# interface.net
KiCad netlist of a schematic drawn in Altium Designer
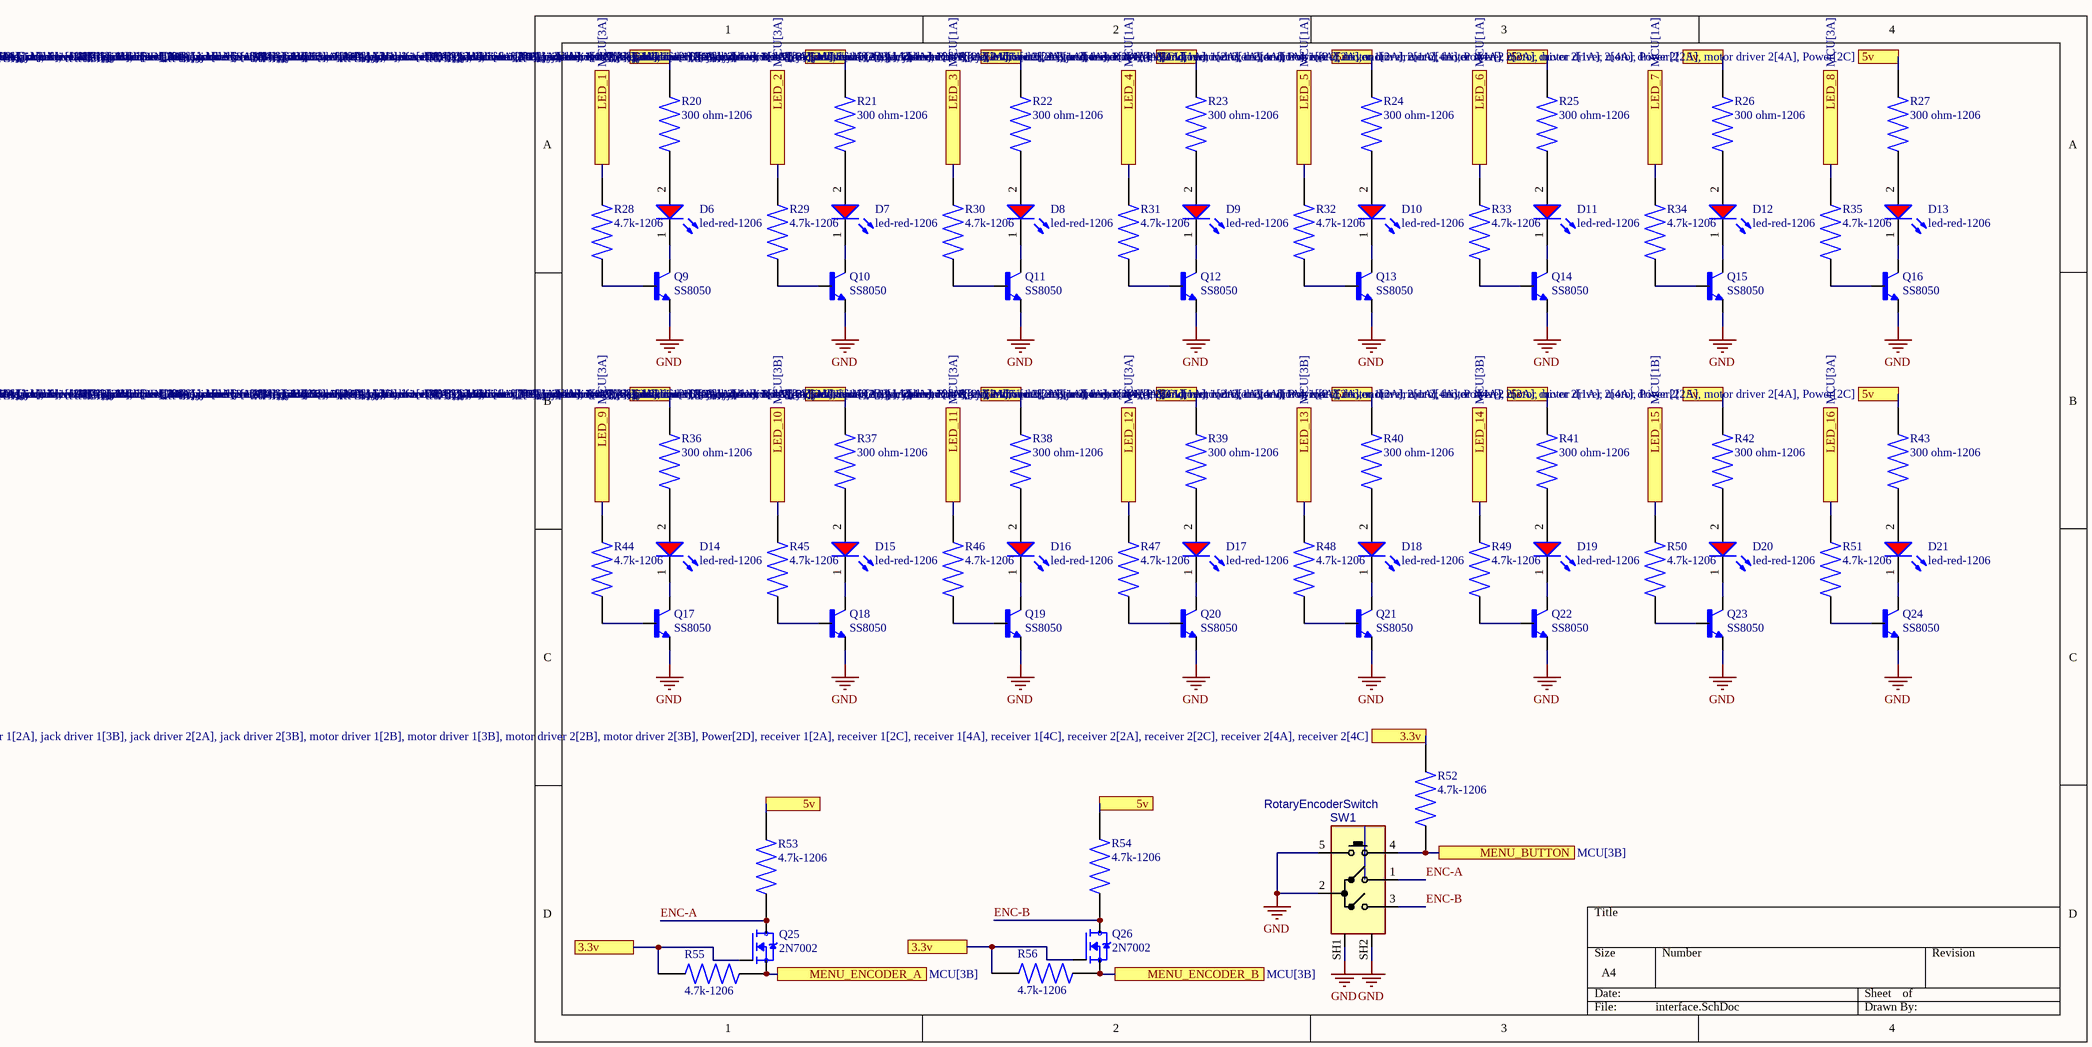
[diagram p0: interface.SchDoc]

(export (version "E")
  (design (tool "Eeschema 10.0.6"))
  (components
    (comp (ref "D6")
      (value "led-red-1206")
      (footprint "WL-SMRW_1206 dome_normal use")
      (description "WL-SMRW Mono-color Reverse mount Waterclear, SMT, size 1206 dome, Red, 2V, 20°")
      (fields
        (field (name "MANUFACTURER PART NUMBER") "156120RS82500")
        (field (name "MANUFACTURER") "Wurth Elektronik")
      )
      (libsource (lib "led-1206") (part "156120RS82500"))
    )
    (comp (ref "D7")
      (value "led-red-1206")
      (footprint "WL-SMRW_1206 dome_normal use")
      (description "WL-SMRW Mono-color Reverse mount Waterclear, SMT, size 1206 dome, Red, 2V, 20°")
      (fields
        (field (name "MANUFACTURER PART NUMBER") "156120RS82500")
        (field (name "MANUFACTURER") "Wurth Elektronik")
      )
      (libsource (lib "led-1206") (part "156120RS82500"))
    )
    (comp (ref "D8")
      (value "led-red-1206")
      (footprint "WL-SMRW_1206 dome_normal use")
      (description "WL-SMRW Mono-color Reverse mount Waterclear, SMT, size 1206 dome, Red, 2V, 20°")
      (fields
        (field (name "MANUFACTURER PART NUMBER") "156120RS82500")
        (field (name "MANUFACTURER") "Wurth Elektronik")
      )
      (libsource (lib "led-1206") (part "156120RS82500"))
    )
    (comp (ref "D9")
      (value "led-red-1206")
      (footprint "WL-SMRW_1206 dome_normal use")
      (description "WL-SMRW Mono-color Reverse mount Waterclear, SMT, size 1206 dome, Red, 2V, 20°")
      (fields
        (field (name "MANUFACTURER PART NUMBER") "156120RS82500")
        (field (name "MANUFACTURER") "Wurth Elektronik")
      )
      (libsource (lib "led-1206") (part "156120RS82500"))
    )
    (comp (ref "D10")
      (value "led-red-1206")
      (footprint "WL-SMRW_1206 dome_normal use")
      (description "WL-SMRW Mono-color Reverse mount Waterclear, SMT, size 1206 dome, Red, 2V, 20°")
      (fields
        (field (name "MANUFACTURER PART NUMBER") "156120RS82500")
        (field (name "MANUFACTURER") "Wurth Elektronik")
      )
      (libsource (lib "led-1206") (part "156120RS82500"))
    )
    (comp (ref "D11")
      (value "led-red-1206")
      (footprint "WL-SMRW_1206 dome_normal use")
      (description "WL-SMRW Mono-color Reverse mount Waterclear, SMT, size 1206 dome, Red, 2V, 20°")
      (fields
        (field (name "MANUFACTURER PART NUMBER") "156120RS82500")
        (field (name "MANUFACTURER") "Wurth Elektronik")
      )
      (libsource (lib "led-1206") (part "156120RS82500"))
    )
    (comp (ref "D12")
      (value "led-red-1206")
      (footprint "WL-SMRW_1206 dome_normal use")
      (description "WL-SMRW Mono-color Reverse mount Waterclear, SMT, size 1206 dome, Red, 2V, 20°")
      (fields
        (field (name "MANUFACTURER PART NUMBER") "156120RS82500")
        (field (name "MANUFACTURER") "Wurth Elektronik")
      )
      (libsource (lib "led-1206") (part "156120RS82500"))
    )
    (comp (ref "D13")
      (value "led-red-1206")
      (footprint "WL-SMRW_1206 dome_normal use")
      (description "WL-SMRW Mono-color Reverse mount Waterclear, SMT, size 1206 dome, Red, 2V, 20°")
      (fields
        (field (name "MANUFACTURER PART NUMBER") "156120RS82500")
        (field (name "MANUFACTURER") "Wurth Elektronik")
      )
      (libsource (lib "led-1206") (part "156120RS82500"))
    )
    (comp (ref "D14")
      (value "led-red-1206")
      (footprint "WL-SMRW_1206 dome_normal use")
      (description "WL-SMRW Mono-color Reverse mount Waterclear, SMT, size 1206 dome, Red, 2V, 20°")
      (fields
        (field (name "MANUFACTURER PART NUMBER") "156120RS82500")
        (field (name "MANUFACTURER") "Wurth Elektronik")
      )
      (libsource (lib "led-1206") (part "156120RS82500"))
    )
    (comp (ref "D15")
      (value "led-red-1206")
      (footprint "WL-SMRW_1206 dome_normal use")
      (description "WL-SMRW Mono-color Reverse mount Waterclear, SMT, size 1206 dome, Red, 2V, 20°")
      (fields
        (field (name "MANUFACTURER PART NUMBER") "156120RS82500")
        (field (name "MANUFACTURER") "Wurth Elektronik")
      )
      (libsource (lib "led-1206") (part "156120RS82500"))
    )
    (comp (ref "D16")
      (value "led-red-1206")
      (footprint "WL-SMRW_1206 dome_normal use")
      (description "WL-SMRW Mono-color Reverse mount Waterclear, SMT, size 1206 dome, Red, 2V, 20°")
      (fields
        (field (name "MANUFACTURER PART NUMBER") "156120RS82500")
        (field (name "MANUFACTURER") "Wurth Elektronik")
      )
      (libsource (lib "led-1206") (part "156120RS82500"))
    )
    (comp (ref "D17")
      (value "led-red-1206")
      (footprint "WL-SMRW_1206 dome_normal use")
      (description "WL-SMRW Mono-color Reverse mount Waterclear, SMT, size 1206 dome, Red, 2V, 20°")
      (fields
        (field (name "MANUFACTURER PART NUMBER") "156120RS82500")
        (field (name "MANUFACTURER") "Wurth Elektronik")
      )
      (libsource (lib "led-1206") (part "156120RS82500"))
    )
    (comp (ref "D18")
      (value "led-red-1206")
      (footprint "WL-SMRW_1206 dome_normal use")
      (description "WL-SMRW Mono-color Reverse mount Waterclear, SMT, size 1206 dome, Red, 2V, 20°")
      (fields
        (field (name "MANUFACTURER PART NUMBER") "156120RS82500")
        (field (name "MANUFACTURER") "Wurth Elektronik")
      )
      (libsource (lib "led-1206") (part "156120RS82500"))
    )
    (comp (ref "D19")
      (value "led-red-1206")
      (footprint "WL-SMRW_1206 dome_normal use")
      (description "WL-SMRW Mono-color Reverse mount Waterclear, SMT, size 1206 dome, Red, 2V, 20°")
      (fields
        (field (name "MANUFACTURER PART NUMBER") "156120RS82500")
        (field (name "MANUFACTURER") "Wurth Elektronik")
      )
      (libsource (lib "led-1206") (part "156120RS82500"))
    )
    (comp (ref "D20")
      (value "led-red-1206")
      (footprint "WL-SMRW_1206 dome_normal use")
      (description "WL-SMRW Mono-color Reverse mount Waterclear, SMT, size 1206 dome, Red, 2V, 20°")
      (fields
        (field (name "MANUFACTURER PART NUMBER") "156120RS82500")
        (field (name "MANUFACTURER") "Wurth Elektronik")
      )
      (libsource (lib "led-1206") (part "156120RS82500"))
    )
    (comp (ref "D21")
      (value "led-red-1206")
      (footprint "WL-SMRW_1206 dome_normal use")
      (description "WL-SMRW Mono-color Reverse mount Waterclear, SMT, size 1206 dome, Red, 2V, 20°")
      (fields
        (field (name "MANUFACTURER PART NUMBER") "156120RS82500")
        (field (name "MANUFACTURER") "Wurth Elektronik")
      )
      (libsource (lib "led-1206") (part "156120RS82500"))
    )
    (comp (ref "Q9")
      (value "SS8050")
      (footprint "TRANS_SS8050-G")
      (description "Bipolar (BJT) Transistor NPN 25 V 1.5 A 100MHz 300 mW Surface Mount SOT-23-3")
      (fields (field (name "DIGI-KEY_PART_NUMBER") "641-1790-2-ND") (field (name "MP") "SS8050G"))
      (libsource (lib "SS8050-G") (part "SS8050-G"))
    )
    (comp (ref "Q10")
      (value "SS8050")
      (footprint "TRANS_SS8050-G")
      (description "Bipolar (BJT) Transistor NPN 25 V 1.5 A 100MHz 300 mW Surface Mount SOT-23-3")
      (fields (field (name "DIGI-KEY_PART_NUMBER") "641-1790-2-ND") (field (name "MP") "SS8050G"))
      (libsource (lib "SS8050-G") (part "SS8050-G"))
    )
    (comp (ref "Q11")
      (value "SS8050")
      (footprint "TRANS_SS8050-G")
      (description "Bipolar (BJT) Transistor NPN 25 V 1.5 A 100MHz 300 mW Surface Mount SOT-23-3")
      (fields (field (name "DIGI-KEY_PART_NUMBER") "641-1790-2-ND") (field (name "MP") "SS8050G"))
      (libsource (lib "SS8050-G") (part "SS8050-G"))
    )
    (comp (ref "Q12")
      (value "SS8050")
      (footprint "TRANS_SS8050-G")
      (description "Bipolar (BJT) Transistor NPN 25 V 1.5 A 100MHz 300 mW Surface Mount SOT-23-3")
      (fields (field (name "DIGI-KEY_PART_NUMBER") "641-1790-2-ND") (field (name "MP") "SS8050G"))
      (libsource (lib "SS8050-G") (part "SS8050-G"))
    )
    (comp (ref "Q13")
      (value "SS8050")
      (footprint "TRANS_SS8050-G")
      (description "Bipolar (BJT) Transistor NPN 25 V 1.5 A 100MHz 300 mW Surface Mount SOT-23-3")
      (fields (field (name "DIGI-KEY_PART_NUMBER") "641-1790-2-ND") (field (name "MP") "SS8050G"))
      (libsource (lib "SS8050-G") (part "SS8050-G"))
    )
    (comp (ref "Q14")
      (value "SS8050")
      (footprint "TRANS_SS8050-G")
      (description "Bipolar (BJT) Transistor NPN 25 V 1.5 A 100MHz 300 mW Surface Mount SOT-23-3")
      (fields (field (name "DIGI-KEY_PART_NUMBER") "641-1790-2-ND") (field (name "MP") "SS8050G"))
      (libsource (lib "SS8050-G") (part "SS8050-G"))
    )
    (comp (ref "Q15")
      (value "SS8050")
      (footprint "TRANS_SS8050-G")
      (description "Bipolar (BJT) Transistor NPN 25 V 1.5 A 100MHz 300 mW Surface Mount SOT-23-3")
      (fields (field (name "DIGI-KEY_PART_NUMBER") "641-1790-2-ND") (field (name "MP") "SS8050G"))
      (libsource (lib "SS8050-G") (part "SS8050-G"))
    )
    (comp (ref "Q16")
      (value "SS8050")
      (footprint "TRANS_SS8050-G")
      (description "Bipolar (BJT) Transistor NPN 25 V 1.5 A 100MHz 300 mW Surface Mount SOT-23-3")
      (fields (field (name "DIGI-KEY_PART_NUMBER") "641-1790-2-ND") (field (name "MP") "SS8050G"))
      (libsource (lib "SS8050-G") (part "SS8050-G"))
    )
    (comp (ref "Q17")
      (value "SS8050")
      (footprint "TRANS_SS8050-G")
      (description "Bipolar (BJT) Transistor NPN 25 V 1.5 A 100MHz 300 mW Surface Mount SOT-23-3")
      (fields (field (name "DIGI-KEY_PART_NUMBER") "641-1790-2-ND") (field (name "MP") "SS8050G"))
      (libsource (lib "SS8050-G") (part "SS8050-G"))
    )
    (comp (ref "Q18")
      (value "SS8050")
      (footprint "TRANS_SS8050-G")
      (description "Bipolar (BJT) Transistor NPN 25 V 1.5 A 100MHz 300 mW Surface Mount SOT-23-3")
      (fields (field (name "DIGI-KEY_PART_NUMBER") "641-1790-2-ND") (field (name "MP") "SS8050G"))
      (libsource (lib "SS8050-G") (part "SS8050-G"))
    )
    (comp (ref "Q19")
      (value "SS8050")
      (footprint "TRANS_SS8050-G")
      (description "Bipolar (BJT) Transistor NPN 25 V 1.5 A 100MHz 300 mW Surface Mount SOT-23-3")
      (fields (field (name "DIGI-KEY_PART_NUMBER") "641-1790-2-ND") (field (name "MP") "SS8050G"))
      (libsource (lib "SS8050-G") (part "SS8050-G"))
    )
    (comp (ref "Q20")
      (value "SS8050")
      (footprint "TRANS_SS8050-G")
      (description "Bipolar (BJT) Transistor NPN 25 V 1.5 A 100MHz 300 mW Surface Mount SOT-23-3")
      (fields (field (name "DIGI-KEY_PART_NUMBER") "641-1790-2-ND") (field (name "MP") "SS8050G"))
      (libsource (lib "SS8050-G") (part "SS8050-G"))
    )
    (comp (ref "Q21")
      (value "SS8050")
      (footprint "TRANS_SS8050-G")
      (description "Bipolar (BJT) Transistor NPN 25 V 1.5 A 100MHz 300 mW Surface Mount SOT-23-3")
      (fields (field (name "DIGI-KEY_PART_NUMBER") "641-1790-2-ND") (field (name "MP") "SS8050G"))
      (libsource (lib "SS8050-G") (part "SS8050-G"))
    )
    (comp (ref "Q22")
      (value "SS8050")
      (footprint "TRANS_SS8050-G")
      (description "Bipolar (BJT) Transistor NPN 25 V 1.5 A 100MHz 300 mW Surface Mount SOT-23-3")
      (fields (field (name "DIGI-KEY_PART_NUMBER") "641-1790-2-ND") (field (name "MP") "SS8050G"))
      (libsource (lib "SS8050-G") (part "SS8050-G"))
    )
    (comp (ref "Q23")
      (value "SS8050")
      (footprint "TRANS_SS8050-G")
      (description "Bipolar (BJT) Transistor NPN 25 V 1.5 A 100MHz 300 mW Surface Mount SOT-23-3")
      (fields (field (name "DIGI-KEY_PART_NUMBER") "641-1790-2-ND") (field (name "MP") "SS8050G"))
      (libsource (lib "SS8050-G") (part "SS8050-G"))
    )
    (comp (ref "Q24")
      (value "SS8050")
      (footprint "TRANS_SS8050-G")
      (description "Bipolar (BJT) Transistor NPN 25 V 1.5 A 100MHz 300 mW Surface Mount SOT-23-3")
      (fields (field (name "DIGI-KEY_PART_NUMBER") "641-1790-2-ND") (field (name "MP") "SS8050G"))
      (libsource (lib "SS8050-G") (part "SS8050-G"))
    )
    (comp (ref "Q25")
      (value "2N7002")
      (footprint "SOT95P240X111-3N")
      (description "N-Channel 60V 280mA (Ta) 350mW (Ta) Surface Mount SOT-23-3 (TO-236)")
      (fields (field (name "MF") "{'manufacturer': u'onsemi'}"))
      (libsource (lib "2N7002-SOT23") (part "2N7002"))
    )
    (comp (ref "Q26")
      (value "2N7002")
      (footprint "SOT95P240X111-3N")
      (description "N-Channel 60V 280mA (Ta) 350mW (Ta) Surface Mount SOT-23-3 (TO-236)")
      (fields (field (name "MF") "{'manufacturer': u'onsemi'}"))
      (libsource (lib "2N7002-SOT23") (part "2N7002"))
    )
    (comp (ref "R20")
      (value "300 ohm-1206")
      (footprint "RESC3015X65N")
      (description "Res Thin Film 1206 10K Ohm 0.1% 1/8W Â±25ppm/Â°C Molded SMD SMD Paper T/R")
      (fields (field (name "MF") "TE Connectivity") (field (name "MP") "CPF1206B10KE1"))
      (libsource (lib "resistor-1206") (part "CPF1206B10KE1"))
    )
    (comp (ref "R21")
      (value "300 ohm-1206")
      (footprint "RESC3015X65N")
      (description "Res Thin Film 1206 10K Ohm 0.1% 1/8W Â±25ppm/Â°C Molded SMD SMD Paper T/R")
      (fields (field (name "MF") "TE Connectivity") (field (name "MP") "CPF1206B10KE1"))
      (libsource (lib "resistor-1206") (part "CPF1206B10KE1"))
    )
    (comp (ref "R22")
      (value "300 ohm-1206")
      (footprint "RESC3015X65N")
      (description "Res Thin Film 1206 10K Ohm 0.1% 1/8W Â±25ppm/Â°C Molded SMD SMD Paper T/R")
      (fields (field (name "MF") "TE Connectivity") (field (name "MP") "CPF1206B10KE1"))
      (libsource (lib "resistor-1206") (part "CPF1206B10KE1"))
    )
    (comp (ref "R23")
      (value "300 ohm-1206")
      (footprint "RESC3015X65N")
      (description "Res Thin Film 1206 10K Ohm 0.1% 1/8W Â±25ppm/Â°C Molded SMD SMD Paper T/R")
      (fields (field (name "MF") "TE Connectivity") (field (name "MP") "CPF1206B10KE1"))
      (libsource (lib "resistor-1206") (part "CPF1206B10KE1"))
    )
    (comp (ref "R24")
      (value "300 ohm-1206")
      (footprint "RESC3015X65N")
      (description "Res Thin Film 1206 10K Ohm 0.1% 1/8W Â±25ppm/Â°C Molded SMD SMD Paper T/R")
      (fields (field (name "MF") "TE Connectivity") (field (name "MP") "CPF1206B10KE1"))
      (libsource (lib "resistor-1206") (part "CPF1206B10KE1"))
    )
    (comp (ref "R25")
      (value "300 ohm-1206")
      (footprint "RESC3015X65N")
      (description "Res Thin Film 1206 10K Ohm 0.1% 1/8W Â±25ppm/Â°C Molded SMD SMD Paper T/R")
      (fields (field (name "MF") "TE Connectivity") (field (name "MP") "CPF1206B10KE1"))
      (libsource (lib "resistor-1206") (part "CPF1206B10KE1"))
    )
    (comp (ref "R26")
      (value "300 ohm-1206")
      (footprint "RESC3015X65N")
      (description "Res Thin Film 1206 10K Ohm 0.1% 1/8W Â±25ppm/Â°C Molded SMD SMD Paper T/R")
      (fields (field (name "MF") "TE Connectivity") (field (name "MP") "CPF1206B10KE1"))
      (libsource (lib "resistor-1206") (part "CPF1206B10KE1"))
    )
    (comp (ref "R27")
      (value "300 ohm-1206")
      (footprint "RESC3015X65N")
      (description "Res Thin Film 1206 10K Ohm 0.1% 1/8W Â±25ppm/Â°C Molded SMD SMD Paper T/R")
      (fields (field (name "MF") "TE Connectivity") (field (name "MP") "CPF1206B10KE1"))
      (libsource (lib "resistor-1206") (part "CPF1206B10KE1"))
    )
    (comp (ref "R28")
      (value "4.7k-1206")
      (footprint "RESC3015X65N")
      (description "Res Thin Film 1206 10K Ohm 0.1% 1/8W Â±25ppm/Â°C Molded SMD SMD Paper T/R")
      (fields (field (name "MF") "TE Connectivity") (field (name "MP") "CPF1206B10KE1"))
      (libsource (lib "resistor-1206") (part "CPF1206B10KE1"))
    )
    (comp (ref "R29")
      (value "4.7k-1206")
      (footprint "RESC3015X65N")
      (description "Res Thin Film 1206 10K Ohm 0.1% 1/8W Â±25ppm/Â°C Molded SMD SMD Paper T/R")
      (fields (field (name "MF") "TE Connectivity") (field (name "MP") "CPF1206B10KE1"))
      (libsource (lib "resistor-1206") (part "CPF1206B10KE1"))
    )
    (comp (ref "R30")
      (value "4.7k-1206")
      (footprint "RESC3015X65N")
      (description "Res Thin Film 1206 10K Ohm 0.1% 1/8W Â±25ppm/Â°C Molded SMD SMD Paper T/R")
      (fields (field (name "MF") "TE Connectivity") (field (name "MP") "CPF1206B10KE1"))
      (libsource (lib "resistor-1206") (part "CPF1206B10KE1"))
    )
    (comp (ref "R31")
      (value "4.7k-1206")
      (footprint "RESC3015X65N")
      (description "Res Thin Film 1206 10K Ohm 0.1% 1/8W Â±25ppm/Â°C Molded SMD SMD Paper T/R")
      (fields (field (name "MF") "TE Connectivity") (field (name "MP") "CPF1206B10KE1"))
      (libsource (lib "resistor-1206") (part "CPF1206B10KE1"))
    )
    (comp (ref "R32")
      (value "4.7k-1206")
      (footprint "RESC3015X65N")
      (description "Res Thin Film 1206 10K Ohm 0.1% 1/8W Â±25ppm/Â°C Molded SMD SMD Paper T/R")
      (fields (field (name "MF") "TE Connectivity") (field (name "MP") "CPF1206B10KE1"))
      (libsource (lib "resistor-1206") (part "CPF1206B10KE1"))
    )
    (comp (ref "R33")
      (value "4.7k-1206")
      (footprint "RESC3015X65N")
      (description "Res Thin Film 1206 10K Ohm 0.1% 1/8W Â±25ppm/Â°C Molded SMD SMD Paper T/R")
      (fields (field (name "MF") "TE Connectivity") (field (name "MP") "CPF1206B10KE1"))
      (libsource (lib "resistor-1206") (part "CPF1206B10KE1"))
    )
    (comp (ref "R34")
      (value "4.7k-1206")
      (footprint "RESC3015X65N")
      (description "Res Thin Film 1206 10K Ohm 0.1% 1/8W Â±25ppm/Â°C Molded SMD SMD Paper T/R")
      (fields (field (name "MF") "TE Connectivity") (field (name "MP") "CPF1206B10KE1"))
      (libsource (lib "resistor-1206") (part "CPF1206B10KE1"))
    )
    (comp (ref "R35")
      (value "4.7k-1206")
      (footprint "RESC3015X65N")
      (description "Res Thin Film 1206 10K Ohm 0.1% 1/8W Â±25ppm/Â°C Molded SMD SMD Paper T/R")
      (fields (field (name "MF") "TE Connectivity") (field (name "MP") "CPF1206B10KE1"))
      (libsource (lib "resistor-1206") (part "CPF1206B10KE1"))
    )
    (comp (ref "R36")
      (value "300 ohm-1206")
      (footprint "RESC3015X65N")
      (description "Res Thin Film 1206 10K Ohm 0.1% 1/8W Â±25ppm/Â°C Molded SMD SMD Paper T/R")
      (fields (field (name "MF") "TE Connectivity") (field (name "MP") "CPF1206B10KE1"))
      (libsource (lib "resistor-1206") (part "CPF1206B10KE1"))
    )
    (comp (ref "R37")
      (value "300 ohm-1206")
      (footprint "RESC3015X65N")
      (description "Res Thin Film 1206 10K Ohm 0.1% 1/8W Â±25ppm/Â°C Molded SMD SMD Paper T/R")
      (fields (field (name "MF") "TE Connectivity") (field (name "MP") "CPF1206B10KE1"))
      (libsource (lib "resistor-1206") (part "CPF1206B10KE1"))
    )
    (comp (ref "R38")
      (value "300 ohm-1206")
      (footprint "RESC3015X65N")
      (description "Res Thin Film 1206 10K Ohm 0.1% 1/8W Â±25ppm/Â°C Molded SMD SMD Paper T/R")
      (fields (field (name "MF") "TE Connectivity") (field (name "MP") "CPF1206B10KE1"))
      (libsource (lib "resistor-1206") (part "CPF1206B10KE1"))
    )
    (comp (ref "R39")
      (value "300 ohm-1206")
      (footprint "RESC3015X65N")
      (description "Res Thin Film 1206 10K Ohm 0.1% 1/8W Â±25ppm/Â°C Molded SMD SMD Paper T/R")
      (fields (field (name "MF") "TE Connectivity") (field (name "MP") "CPF1206B10KE1"))
      (libsource (lib "resistor-1206") (part "CPF1206B10KE1"))
    )
    (comp (ref "R40")
      (value "300 ohm-1206")
      (footprint "RESC3015X65N")
      (description "Res Thin Film 1206 10K Ohm 0.1% 1/8W Â±25ppm/Â°C Molded SMD SMD Paper T/R")
      (fields (field (name "MF") "TE Connectivity") (field (name "MP") "CPF1206B10KE1"))
      (libsource (lib "resistor-1206") (part "CPF1206B10KE1"))
    )
    (comp (ref "R41")
      (value "300 ohm-1206")
      (footprint "RESC3015X65N")
      (description "Res Thin Film 1206 10K Ohm 0.1% 1/8W Â±25ppm/Â°C Molded SMD SMD Paper T/R")
      (fields (field (name "MF") "TE Connectivity") (field (name "MP") "CPF1206B10KE1"))
      (libsource (lib "resistor-1206") (part "CPF1206B10KE1"))
    )
    (comp (ref "R42")
      (value "300 ohm-1206")
      (footprint "RESC3015X65N")
      (description "Res Thin Film 1206 10K Ohm 0.1% 1/8W Â±25ppm/Â°C Molded SMD SMD Paper T/R")
      (fields (field (name "MF") "TE Connectivity") (field (name "MP") "CPF1206B10KE1"))
      (libsource (lib "resistor-1206") (part "CPF1206B10KE1"))
    )
    (comp (ref "R43")
      (value "300 ohm-1206")
      (footprint "RESC3015X65N")
      (description "Res Thin Film 1206 10K Ohm 0.1% 1/8W Â±25ppm/Â°C Molded SMD SMD Paper T/R")
      (fields (field (name "MF") "TE Connectivity") (field (name "MP") "CPF1206B10KE1"))
      (libsource (lib "resistor-1206") (part "CPF1206B10KE1"))
    )
    (comp (ref "R44")
      (value "4.7k-1206")
      (footprint "RESC3015X65N")
      (description "Res Thin Film 1206 10K Ohm 0.1% 1/8W Â±25ppm/Â°C Molded SMD SMD Paper T/R")
      (fields (field (name "MF") "TE Connectivity") (field (name "MP") "CPF1206B10KE1"))
      (libsource (lib "resistor-1206") (part "CPF1206B10KE1"))
    )
    (comp (ref "R45")
      (value "4.7k-1206")
      (footprint "RESC3015X65N")
      (description "Res Thin Film 1206 10K Ohm 0.1% 1/8W Â±25ppm/Â°C Molded SMD SMD Paper T/R")
      (fields (field (name "MF") "TE Connectivity") (field (name "MP") "CPF1206B10KE1"))
      (libsource (lib "resistor-1206") (part "CPF1206B10KE1"))
    )
    (comp (ref "R46")
      (value "4.7k-1206")
      (footprint "RESC3015X65N")
      (description "Res Thin Film 1206 10K Ohm 0.1% 1/8W Â±25ppm/Â°C Molded SMD SMD Paper T/R")
      (fields (field (name "MF") "TE Connectivity") (field (name "MP") "CPF1206B10KE1"))
      (libsource (lib "resistor-1206") (part "CPF1206B10KE1"))
    )
    (comp (ref "R47")
      (value "4.7k-1206")
      (footprint "RESC3015X65N")
      (description "Res Thin Film 1206 10K Ohm 0.1% 1/8W Â±25ppm/Â°C Molded SMD SMD Paper T/R")
      (fields (field (name "MF") "TE Connectivity") (field (name "MP") "CPF1206B10KE1"))
      (libsource (lib "resistor-1206") (part "CPF1206B10KE1"))
    )
    (comp (ref "R48")
      (value "4.7k-1206")
      (footprint "RESC3015X65N")
      (description "Res Thin Film 1206 10K Ohm 0.1% 1/8W Â±25ppm/Â°C Molded SMD SMD Paper T/R")
      (fields (field (name "MF") "TE Connectivity") (field (name "MP") "CPF1206B10KE1"))
      (libsource (lib "resistor-1206") (part "CPF1206B10KE1"))
    )
    (comp (ref "R49")
      (value "4.7k-1206")
      (footprint "RESC3015X65N")
      (description "Res Thin Film 1206 10K Ohm 0.1% 1/8W Â±25ppm/Â°C Molded SMD SMD Paper T/R")
      (fields (field (name "MF") "TE Connectivity") (field (name "MP") "CPF1206B10KE1"))
      (libsource (lib "resistor-1206") (part "CPF1206B10KE1"))
    )
    (comp (ref "R50")
      (value "4.7k-1206")
      (footprint "RESC3015X65N")
      (description "Res Thin Film 1206 10K Ohm 0.1% 1/8W Â±25ppm/Â°C Molded SMD SMD Paper T/R")
      (fields (field (name "MF") "TE Connectivity") (field (name "MP") "CPF1206B10KE1"))
      (libsource (lib "resistor-1206") (part "CPF1206B10KE1"))
    )
    (comp (ref "R51")
      (value "4.7k-1206")
      (footprint "RESC3015X65N")
      (description "Res Thin Film 1206 10K Ohm 0.1% 1/8W Â±25ppm/Â°C Molded SMD SMD Paper T/R")
      (fields (field (name "MF") "TE Connectivity") (field (name "MP") "CPF1206B10KE1"))
      (libsource (lib "resistor-1206") (part "CPF1206B10KE1"))
    )
    (comp (ref "R52")
      (value "4.7k-1206")
      (footprint "RESC3015X65N")
      (description "Res Thin Film 1206 10K Ohm 0.1% 1/8W Â±25ppm/Â°C Molded SMD SMD Paper T/R")
      (fields (field (name "MF") "TE Connectivity") (field (name "MP") "CPF1206B10KE1"))
      (libsource (lib "resistor-1206") (part "CPF1206B10KE1"))
    )
    (comp (ref "R53")
      (value "4.7k-1206")
      (footprint "RESC3015X65N")
      (description "Res Thin Film 1206 10K Ohm 0.1% 1/8W Â±25ppm/Â°C Molded SMD SMD Paper T/R")
      (fields (field (name "MF") "TE Connectivity") (field (name "MP") "CPF1206B10KE1"))
      (libsource (lib "resistor-1206") (part "CPF1206B10KE1"))
    )
    (comp (ref "R54")
      (value "4.7k-1206")
      (footprint "RESC3015X65N")
      (description "Res Thin Film 1206 10K Ohm 0.1% 1/8W Â±25ppm/Â°C Molded SMD SMD Paper T/R")
      (fields (field (name "MF") "TE Connectivity") (field (name "MP") "CPF1206B10KE1"))
      (libsource (lib "resistor-1206") (part "CPF1206B10KE1"))
    )
    (comp (ref "R55")
      (value "4.7k-1206")
      (footprint "RESC3015X65N")
      (description "Res Thin Film 1206 10K Ohm 0.1% 1/8W Â±25ppm/Â°C Molded SMD SMD Paper T/R")
      (fields (field (name "MF") "TE Connectivity") (field (name "MP") "CPF1206B10KE1"))
      (libsource (lib "resistor-1206") (part "CPF1206B10KE1"))
    )
    (comp (ref "R56")
      (value "4.7k-1206")
      (footprint "RESC3015X65N")
      (description "Res Thin Film 1206 10K Ohm 0.1% 1/8W Â±25ppm/Â°C Molded SMD SMD Paper T/R")
      (fields (field (name "MF") "TE Connectivity") (field (name "MP") "CPF1206B10KE1"))
      (libsource (lib "resistor-1206") (part "CPF1206B10KE1"))
    )
    (comp (ref "SW1")
      (value "RotaryEncoderSwitch")
      (footprint "SWROT_11MM")
      (description "SWITCH, ROTARY Encoder, 11mm Metal Shaft")
      (fields (field (name "MANF") "Alpha") (field (name "MANF_PART#") "RE111F-41B3N-15F-20P"))
      (libsource (lib "rotary encoder") (part "SWROT_11MM"))
    )
  )
  (nets
    (net (code "1") (name "/3.3v") (class "Default")
      (node (ref "Q25") (pin "1") (pinfunction "G_1") (pintype "passive"))
      (node (ref "Q26") (pin "1") (pinfunction "G_1") (pintype "passive"))
      (node (ref "R52") (pin "2") (pinfunction "2_2") (pintype "passive"))
      (node (ref "R55") (pin "1") (pinfunction "1_1") (pintype "passive"))
      (node (ref "R56") (pin "2") (pinfunction "2_2") (pintype "passive"))
    )
    (net (code "2") (name "/5v") (class "Default")
      (node (ref "R20") (pin "2") (pinfunction "2_2") (pintype "passive"))
      (node (ref "R21") (pin "2") (pinfunction "2_2") (pintype "passive"))
      (node (ref "R22") (pin "2") (pinfunction "2_2") (pintype "passive"))
      (node (ref "R23") (pin "2") (pinfunction "2_2") (pintype "passive"))
      (node (ref "R24") (pin "2") (pinfunction "2_2") (pintype "passive"))
      (node (ref "R25") (pin "2") (pinfunction "2_2") (pintype "passive"))
      (node (ref "R26") (pin "2") (pinfunction "2_2") (pintype "passive"))
      (node (ref "R27") (pin "2") (pinfunction "2_2") (pintype "passive"))
      (node (ref "R36") (pin "2") (pinfunction "2_2") (pintype "passive"))
      (node (ref "R37") (pin "2") (pinfunction "2_2") (pintype "passive"))
      (node (ref "R38") (pin "2") (pinfunction "2_2") (pintype "passive"))
      (node (ref "R39") (pin "2") (pinfunction "2_2") (pintype "passive"))
      (node (ref "R40") (pin "2") (pinfunction "2_2") (pintype "passive"))
      (node (ref "R41") (pin "2") (pinfunction "2_2") (pintype "passive"))
      (node (ref "R42") (pin "2") (pinfunction "2_2") (pintype "passive"))
      (node (ref "R43") (pin "2") (pinfunction "2_2") (pintype "passive"))
      (node (ref "R53") (pin "2") (pinfunction "2_2") (pintype "passive"))
      (node (ref "R54") (pin "2") (pinfunction "2_2") (pintype "passive"))
    )
    (net (code "3") (name "/ENC-A") (class "Default")
      (node (ref "Q25") (pin "3") (pinfunction "D_3") (pintype "passive"))
      (node (ref "R53") (pin "1") (pinfunction "1_1") (pintype "passive"))
      (node (ref "SW1") (pin "1") (pinfunction "A_1") (pintype "passive"))
    )
    (net (code "4") (name "/ENC-B") (class "Default")
      (node (ref "Q26") (pin "3") (pinfunction "D_3") (pintype "passive"))
      (node (ref "R54") (pin "1") (pinfunction "1_1") (pintype "passive"))
      (node (ref "SW1") (pin "3") (pinfunction "B_3") (pintype "passive"))
    )
    (net (code "5") (name "/LED_1") (class "Default")
      (node (ref "R28") (pin "2") (pinfunction "2_2") (pintype "passive"))
    )
    (net (code "6") (name "/LED_2") (class "Default")
      (node (ref "R29") (pin "2") (pinfunction "2_2") (pintype "passive"))
    )
    (net (code "7") (name "/LED_3") (class "Default")
      (node (ref "R30") (pin "2") (pinfunction "2_2") (pintype "passive"))
    )
    (net (code "8") (name "/LED_4") (class "Default")
      (node (ref "R31") (pin "2") (pinfunction "2_2") (pintype "passive"))
    )
    (net (code "9") (name "/LED_5") (class "Default")
      (node (ref "R32") (pin "2") (pinfunction "2_2") (pintype "passive"))
    )
    (net (code "10") (name "/LED_6") (class "Default")
      (node (ref "R33") (pin "2") (pinfunction "2_2") (pintype "passive"))
    )
    (net (code "11") (name "/LED_7") (class "Default")
      (node (ref "R34") (pin "2") (pinfunction "2_2") (pintype "passive"))
    )
    (net (code "12") (name "/LED_8") (class "Default")
      (node (ref "R35") (pin "2") (pinfunction "2_2") (pintype "passive"))
    )
    (net (code "13") (name "/LED_9") (class "Default")
      (node (ref "R44") (pin "2") (pinfunction "2_2") (pintype "passive"))
    )
    (net (code "14") (name "/LED_10") (class "Default")
      (node (ref "R45") (pin "2") (pinfunction "2_2") (pintype "passive"))
    )
    (net (code "15") (name "/LED_11") (class "Default")
      (node (ref "R46") (pin "2") (pinfunction "2_2") (pintype "passive"))
    )
    (net (code "16") (name "/LED_12") (class "Default")
      (node (ref "R47") (pin "2") (pinfunction "2_2") (pintype "passive"))
    )
    (net (code "17") (name "/LED_13") (class "Default")
      (node (ref "R48") (pin "2") (pinfunction "2_2") (pintype "passive"))
    )
    (net (code "18") (name "/LED_14") (class "Default")
      (node (ref "R49") (pin "2") (pinfunction "2_2") (pintype "passive"))
    )
    (net (code "19") (name "/LED_15") (class "Default")
      (node (ref "R50") (pin "2") (pinfunction "2_2") (pintype "passive"))
    )
    (net (code "20") (name "/LED_16") (class "Default")
      (node (ref "R51") (pin "2") (pinfunction "2_2") (pintype "passive"))
    )
    (net (code "21") (name "/MENU_BUTTON") (class "Default")
      (node (ref "R52") (pin "1") (pinfunction "1_1") (pintype "passive"))
      (node (ref "SW1") (pin "4") (pinfunction "E_4") (pintype "passive"))
    )
    (net (code "22") (name "/MENU_ENCODER_A") (class "Default")
      (node (ref "Q25") (pin "2") (pinfunction "S_2") (pintype "passive"))
      (node (ref "R55") (pin "2") (pinfunction "2_2") (pintype "passive"))
    )
    (net (code "23") (name "/MENU_ENCODER_B") (class "Default")
      (node (ref "Q26") (pin "2") (pinfunction "S_2") (pintype "passive"))
      (node (ref "R56") (pin "1") (pinfunction "1_1") (pintype "passive"))
    )
    (net (code "24") (name "GND") (class "Default")
      (node (ref "Q10") (pin "2") (pinfunction "E_2") (pintype "passive"))
      (node (ref "Q11") (pin "2") (pinfunction "E_2") (pintype "passive"))
      (node (ref "Q12") (pin "2") (pinfunction "E_2") (pintype "passive"))
      (node (ref "Q13") (pin "2") (pinfunction "E_2") (pintype "passive"))
      (node (ref "Q14") (pin "2") (pinfunction "E_2") (pintype "passive"))
      (node (ref "Q15") (pin "2") (pinfunction "E_2") (pintype "passive"))
      (node (ref "Q16") (pin "2") (pinfunction "E_2") (pintype "passive"))
      (node (ref "Q17") (pin "2") (pinfunction "E_2") (pintype "passive"))
      (node (ref "Q18") (pin "2") (pinfunction "E_2") (pintype "passive"))
      (node (ref "Q19") (pin "2") (pinfunction "E_2") (pintype "passive"))
      (node (ref "Q20") (pin "2") (pinfunction "E_2") (pintype "passive"))
      (node (ref "Q21") (pin "2") (pinfunction "E_2") (pintype "passive"))
      (node (ref "Q22") (pin "2") (pinfunction "E_2") (pintype "passive"))
      (node (ref "Q23") (pin "2") (pinfunction "E_2") (pintype "passive"))
      (node (ref "Q24") (pin "2") (pinfunction "E_2") (pintype "passive"))
      (node (ref "Q9") (pin "2") (pinfunction "E_2") (pintype "passive"))
      (node (ref "SW1") (pin "2") (pinfunction "C_2") (pintype "passive"))
      (node (ref "SW1") (pin "5") (pinfunction "D_5") (pintype "passive"))
      (node (ref "SW1") (pin "SH1") (pinfunction "SH1_SH1") (pintype "passive"))
      (node (ref "SW1") (pin "SH2") (pinfunction "SH2_SH2") (pintype "passive"))
    )
    (net (code "25") (name "Net-(D6-A)") (class "Default")
      (node (ref "D6") (pin "2") (pinfunction "A_2") (pintype "passive"))
      (node (ref "R20") (pin "1") (pinfunction "1_1") (pintype "passive"))
    )
    (net (code "26") (name "Net-(D6-K)") (class "Default")
      (node (ref "D6") (pin "1") (pinfunction "K_1") (pintype "passive"))
      (node (ref "Q9") (pin "3") (pinfunction "C_3") (pintype "passive"))
    )
    (net (code "27") (name "Net-(D7-A)") (class "Default")
      (node (ref "D7") (pin "2") (pinfunction "A_2") (pintype "passive"))
      (node (ref "R21") (pin "1") (pinfunction "1_1") (pintype "passive"))
    )
    (net (code "28") (name "Net-(D7-K)") (class "Default")
      (node (ref "D7") (pin "1") (pinfunction "K_1") (pintype "passive"))
      (node (ref "Q10") (pin "3") (pinfunction "C_3") (pintype "passive"))
    )
    (net (code "29") (name "Net-(D8-A)") (class "Default")
      (node (ref "D8") (pin "2") (pinfunction "A_2") (pintype "passive"))
      (node (ref "R22") (pin "1") (pinfunction "1_1") (pintype "passive"))
    )
    (net (code "30") (name "Net-(D8-K)") (class "Default")
      (node (ref "D8") (pin "1") (pinfunction "K_1") (pintype "passive"))
      (node (ref "Q11") (pin "3") (pinfunction "C_3") (pintype "passive"))
    )
    (net (code "31") (name "Net-(D9-A)") (class "Default")
      (node (ref "D9") (pin "2") (pinfunction "A_2") (pintype "passive"))
      (node (ref "R23") (pin "1") (pinfunction "1_1") (pintype "passive"))
    )
    (net (code "32") (name "Net-(D9-K)") (class "Default")
      (node (ref "D9") (pin "1") (pinfunction "K_1") (pintype "passive"))
      (node (ref "Q12") (pin "3") (pinfunction "C_3") (pintype "passive"))
    )
    (net (code "33") (name "Net-(D10-A)") (class "Default")
      (node (ref "D10") (pin "2") (pinfunction "A_2") (pintype "passive"))
      (node (ref "R24") (pin "1") (pinfunction "1_1") (pintype "passive"))
    )
    (net (code "34") (name "Net-(D10-K)") (class "Default")
      (node (ref "D10") (pin "1") (pinfunction "K_1") (pintype "passive"))
      (node (ref "Q13") (pin "3") (pinfunction "C_3") (pintype "passive"))
    )
    (net (code "35") (name "Net-(D11-A)") (class "Default")
      (node (ref "D11") (pin "2") (pinfunction "A_2") (pintype "passive"))
      (node (ref "R25") (pin "1") (pinfunction "1_1") (pintype "passive"))
    )
    (net (code "36") (name "Net-(D11-K)") (class "Default")
      (node (ref "D11") (pin "1") (pinfunction "K_1") (pintype "passive"))
      (node (ref "Q14") (pin "3") (pinfunction "C_3") (pintype "passive"))
    )
    (net (code "37") (name "Net-(D12-A)") (class "Default")
      (node (ref "D12") (pin "2") (pinfunction "A_2") (pintype "passive"))
      (node (ref "R26") (pin "1") (pinfunction "1_1") (pintype "passive"))
    )
    (net (code "38") (name "Net-(D12-K)") (class "Default")
      (node (ref "D12") (pin "1") (pinfunction "K_1") (pintype "passive"))
      (node (ref "Q15") (pin "3") (pinfunction "C_3") (pintype "passive"))
    )
    (net (code "39") (name "Net-(D13-A)") (class "Default")
      (node (ref "D13") (pin "2") (pinfunction "A_2") (pintype "passive"))
      (node (ref "R27") (pin "1") (pinfunction "1_1") (pintype "passive"))
    )
    (net (code "40") (name "Net-(D13-K)") (class "Default")
      (node (ref "D13") (pin "1") (pinfunction "K_1") (pintype "passive"))
      (node (ref "Q16") (pin "3") (pinfunction "C_3") (pintype "passive"))
    )
    (net (code "41") (name "Net-(D14-A)") (class "Default")
      (node (ref "D14") (pin "2") (pinfunction "A_2") (pintype "passive"))
      (node (ref "R36") (pin "1") (pinfunction "1_1") (pintype "passive"))
    )
    (net (code "42") (name "Net-(D14-K)") (class "Default")
      (node (ref "D14") (pin "1") (pinfunction "K_1") (pintype "passive"))
      (node (ref "Q17") (pin "3") (pinfunction "C_3") (pintype "passive"))
    )
    (net (code "43") (name "Net-(D15-A)") (class "Default")
      (node (ref "D15") (pin "2") (pinfunction "A_2") (pintype "passive"))
      (node (ref "R37") (pin "1") (pinfunction "1_1") (pintype "passive"))
    )
    (net (code "44") (name "Net-(D15-K)") (class "Default")
      (node (ref "D15") (pin "1") (pinfunction "K_1") (pintype "passive"))
      (node (ref "Q18") (pin "3") (pinfunction "C_3") (pintype "passive"))
    )
    (net (code "45") (name "Net-(D16-A)") (class "Default")
      (node (ref "D16") (pin "2") (pinfunction "A_2") (pintype "passive"))
      (node (ref "R38") (pin "1") (pinfunction "1_1") (pintype "passive"))
    )
    (net (code "46") (name "Net-(D16-K)") (class "Default")
      (node (ref "D16") (pin "1") (pinfunction "K_1") (pintype "passive"))
      (node (ref "Q19") (pin "3") (pinfunction "C_3") (pintype "passive"))
    )
    (net (code "47") (name "Net-(D17-A)") (class "Default")
      (node (ref "D17") (pin "2") (pinfunction "A_2") (pintype "passive"))
      (node (ref "R39") (pin "1") (pinfunction "1_1") (pintype "passive"))
    )
    (net (code "48") (name "Net-(D17-K)") (class "Default")
      (node (ref "D17") (pin "1") (pinfunction "K_1") (pintype "passive"))
      (node (ref "Q20") (pin "3") (pinfunction "C_3") (pintype "passive"))
    )
    (net (code "49") (name "Net-(D18-A)") (class "Default")
      (node (ref "D18") (pin "2") (pinfunction "A_2") (pintype "passive"))
      (node (ref "R40") (pin "1") (pinfunction "1_1") (pintype "passive"))
    )
    (net (code "50") (name "Net-(D18-K)") (class "Default")
      (node (ref "D18") (pin "1") (pinfunction "K_1") (pintype "passive"))
      (node (ref "Q21") (pin "3") (pinfunction "C_3") (pintype "passive"))
    )
    (net (code "51") (name "Net-(D19-A)") (class "Default")
      (node (ref "D19") (pin "2") (pinfunction "A_2") (pintype "passive"))
      (node (ref "R41") (pin "1") (pinfunction "1_1") (pintype "passive"))
    )
    (net (code "52") (name "Net-(D19-K)") (class "Default")
      (node (ref "D19") (pin "1") (pinfunction "K_1") (pintype "passive"))
      (node (ref "Q22") (pin "3") (pinfunction "C_3") (pintype "passive"))
    )
    (net (code "53") (name "Net-(D20-A)") (class "Default")
      (node (ref "D20") (pin "2") (pinfunction "A_2") (pintype "passive"))
      (node (ref "R42") (pin "1") (pinfunction "1_1") (pintype "passive"))
    )
    (net (code "54") (name "Net-(D20-K)") (class "Default")
      (node (ref "D20") (pin "1") (pinfunction "K_1") (pintype "passive"))
      (node (ref "Q23") (pin "3") (pinfunction "C_3") (pintype "passive"))
    )
    (net (code "55") (name "Net-(D21-A)") (class "Default")
      (node (ref "D21") (pin "2") (pinfunction "A_2") (pintype "passive"))
      (node (ref "R43") (pin "1") (pinfunction "1_1") (pintype "passive"))
    )
    (net (code "56") (name "Net-(D21-K)") (class "Default")
      (node (ref "D21") (pin "1") (pinfunction "K_1") (pintype "passive"))
      (node (ref "Q24") (pin "3") (pinfunction "C_3") (pintype "passive"))
    )
    (net (code "57") (name "Net-(Q9-B)") (class "Default")
      (node (ref "Q9") (pin "1") (pinfunction "B_1") (pintype "passive"))
      (node (ref "R28") (pin "1") (pinfunction "1_1") (pintype "passive"))
    )
    (net (code "58") (name "Net-(Q10-B)") (class "Default")
      (node (ref "Q10") (pin "1") (pinfunction "B_1") (pintype "passive"))
      (node (ref "R29") (pin "1") (pinfunction "1_1") (pintype "passive"))
    )
    (net (code "59") (name "Net-(Q11-B)") (class "Default")
      (node (ref "Q11") (pin "1") (pinfunction "B_1") (pintype "passive"))
      (node (ref "R30") (pin "1") (pinfunction "1_1") (pintype "passive"))
    )
    (net (code "60") (name "Net-(Q12-B)") (class "Default")
      (node (ref "Q12") (pin "1") (pinfunction "B_1") (pintype "passive"))
      (node (ref "R31") (pin "1") (pinfunction "1_1") (pintype "passive"))
    )
    (net (code "61") (name "Net-(Q13-B)") (class "Default")
      (node (ref "Q13") (pin "1") (pinfunction "B_1") (pintype "passive"))
      (node (ref "R32") (pin "1") (pinfunction "1_1") (pintype "passive"))
    )
    (net (code "62") (name "Net-(Q14-B)") (class "Default")
      (node (ref "Q14") (pin "1") (pinfunction "B_1") (pintype "passive"))
      (node (ref "R33") (pin "1") (pinfunction "1_1") (pintype "passive"))
    )
    (net (code "63") (name "Net-(Q15-B)") (class "Default")
      (node (ref "Q15") (pin "1") (pinfunction "B_1") (pintype "passive"))
      (node (ref "R34") (pin "1") (pinfunction "1_1") (pintype "passive"))
    )
    (net (code "64") (name "Net-(Q16-B)") (class "Default")
      (node (ref "Q16") (pin "1") (pinfunction "B_1") (pintype "passive"))
      (node (ref "R35") (pin "1") (pinfunction "1_1") (pintype "passive"))
    )
    (net (code "65") (name "Net-(Q17-B)") (class "Default")
      (node (ref "Q17") (pin "1") (pinfunction "B_1") (pintype "passive"))
      (node (ref "R44") (pin "1") (pinfunction "1_1") (pintype "passive"))
    )
    (net (code "66") (name "Net-(Q18-B)") (class "Default")
      (node (ref "Q18") (pin "1") (pinfunction "B_1") (pintype "passive"))
      (node (ref "R45") (pin "1") (pinfunction "1_1") (pintype "passive"))
    )
    (net (code "67") (name "Net-(Q19-B)") (class "Default")
      (node (ref "Q19") (pin "1") (pinfunction "B_1") (pintype "passive"))
      (node (ref "R46") (pin "1") (pinfunction "1_1") (pintype "passive"))
    )
    (net (code "68") (name "Net-(Q20-B)") (class "Default")
      (node (ref "Q20") (pin "1") (pinfunction "B_1") (pintype "passive"))
      (node (ref "R47") (pin "1") (pinfunction "1_1") (pintype "passive"))
    )
    (net (code "69") (name "Net-(Q21-B)") (class "Default")
      (node (ref "Q21") (pin "1") (pinfunction "B_1") (pintype "passive"))
      (node (ref "R48") (pin "1") (pinfunction "1_1") (pintype "passive"))
    )
    (net (code "70") (name "Net-(Q22-B)") (class "Default")
      (node (ref "Q22") (pin "1") (pinfunction "B_1") (pintype "passive"))
      (node (ref "R49") (pin "1") (pinfunction "1_1") (pintype "passive"))
    )
    (net (code "71") (name "Net-(Q23-B)") (class "Default")
      (node (ref "Q23") (pin "1") (pinfunction "B_1") (pintype "passive"))
      (node (ref "R50") (pin "1") (pinfunction "1_1") (pintype "passive"))
    )
    (net (code "72") (name "Net-(Q24-B)") (class "Default")
      (node (ref "Q24") (pin "1") (pinfunction "B_1") (pintype "passive"))
      (node (ref "R51") (pin "1") (pinfunction "1_1") (pintype "passive"))
    )
  )
)
